# Freedom_E310.net
KiCad netlist of a schematic drawn in Altium Designer
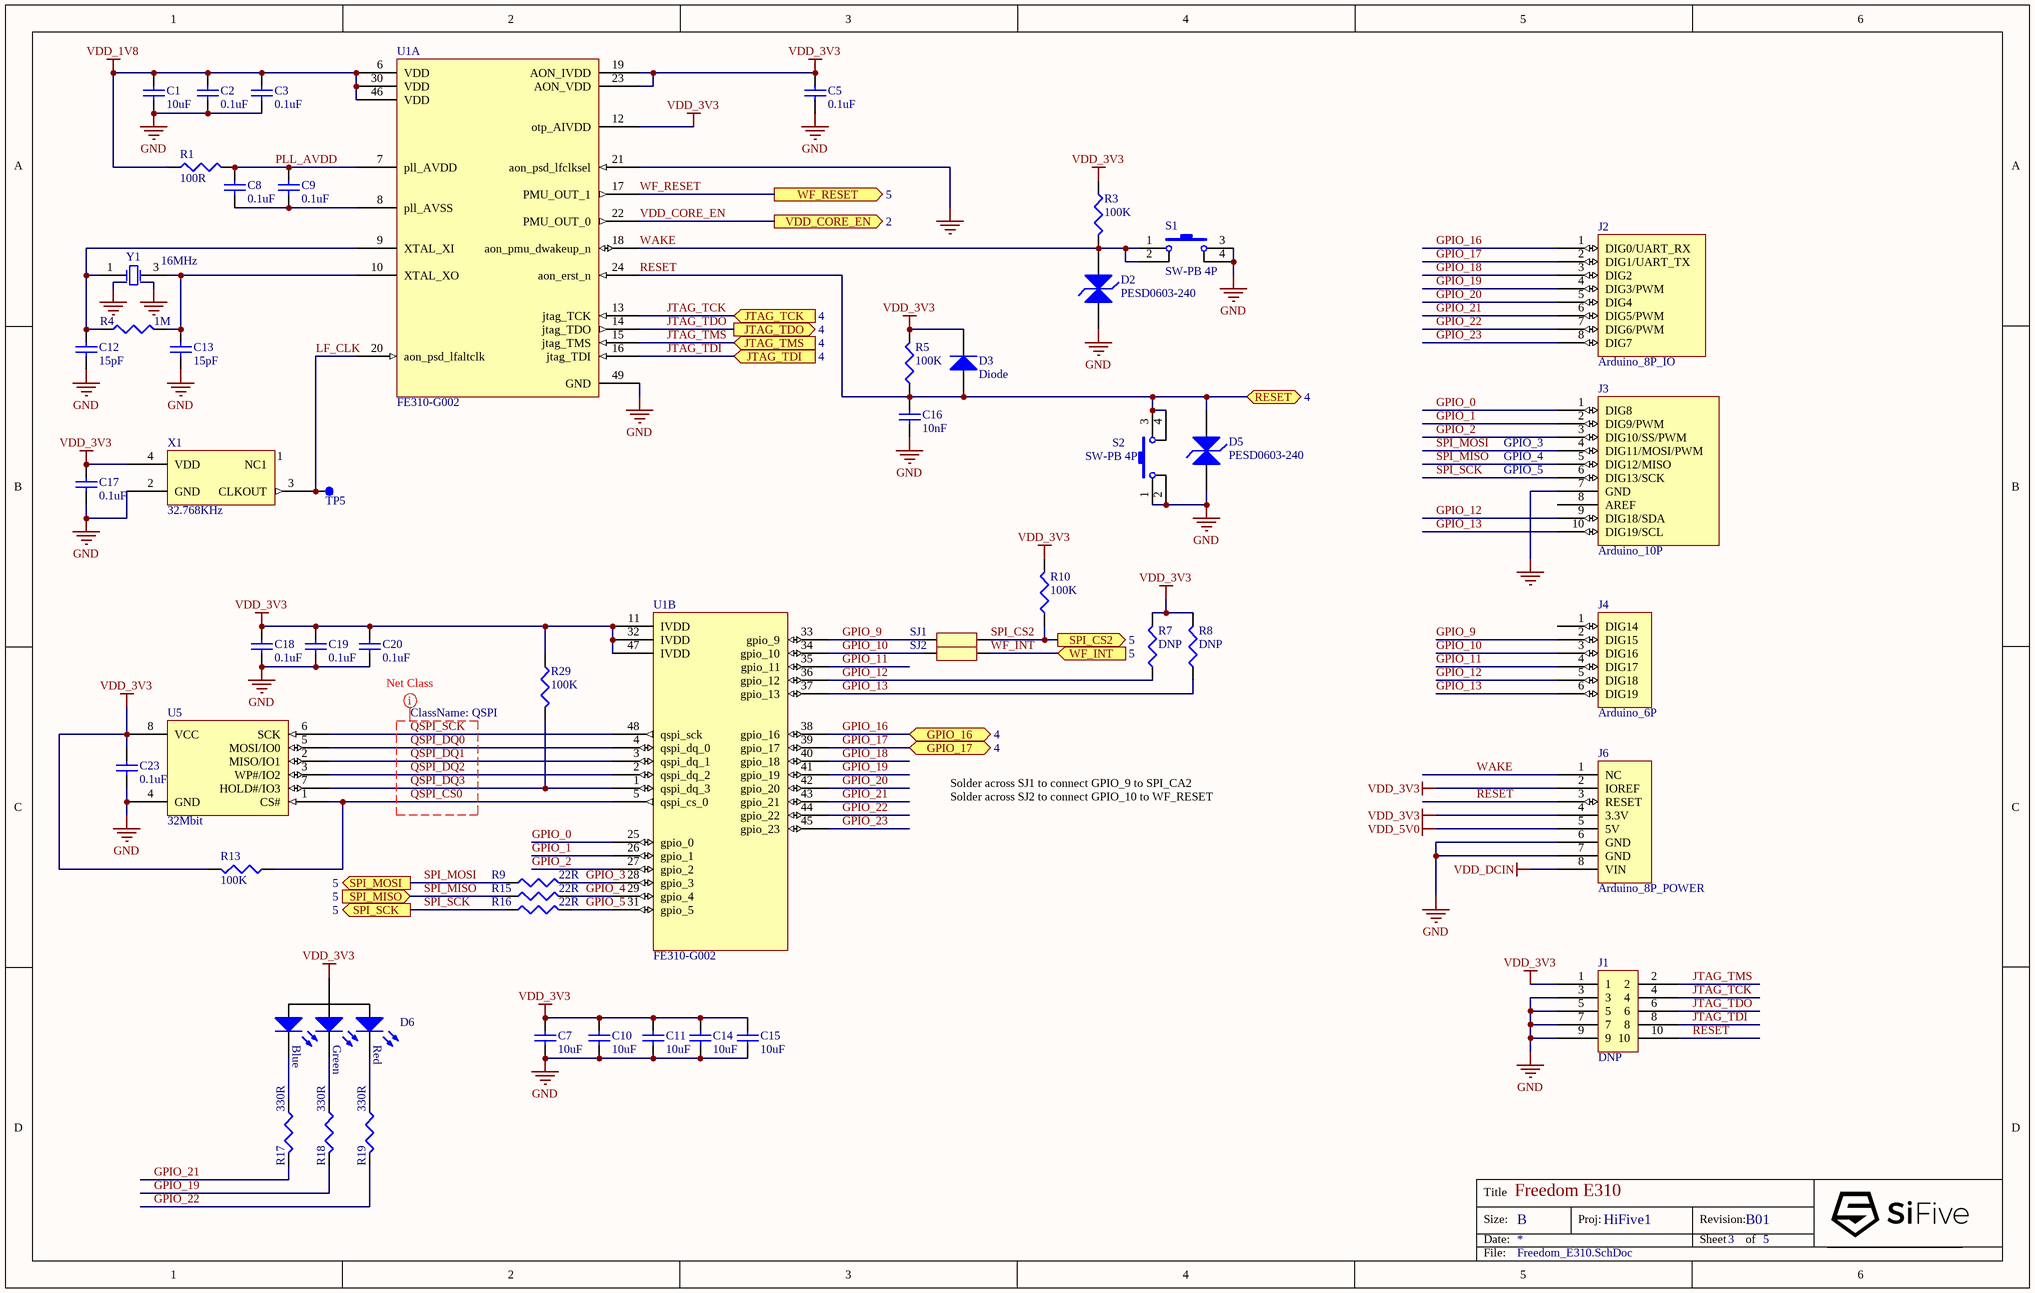
[diagram p0: Freedom_E310.SchDoc]

(export (version "E")
  (design (tool "Eeschema 10.0.6"))
  (components
    (comp (ref "C1")
      (value "10uF")
      (footprint "C0603")
      (description "CAP CER 10UF 10V X5R 0603")
      (fields (field (name "PART NUMBER") "C0100033") (field (name "MANUFACTURER") "Murata Electronics"))
      (libsource (lib "PartLibrary") (part "Capacitor - non polarized"))
    )
    (comp (ref "C2")
      (value "0.1uF")
      (footprint "C0402")
      (description "0.10µF 16V Ceramic Capacitor X7R 0402")
      (fields
        (field (name "PART NUMBER") "C0100004")
        (field (name "MANUFACTURER") "Samsung Electro-Mechanics")
      )
      (libsource (lib "PartLibrary") (part "Capacitor - non polarized"))
    )
    (comp (ref "C3")
      (value "0.1uF")
      (footprint "C0402")
      (description "0.10µF 16V Ceramic Capacitor X7R 0402")
      (fields
        (field (name "PART NUMBER") "C0100004")
        (field (name "MANUFACTURER") "Samsung Electro-Mechanics")
      )
      (libsource (lib "PartLibrary") (part "Capacitor - non polarized"))
    )
    (comp (ref "C5")
      (value "0.1uF")
      (footprint "C0402")
      (description "0.10µF 16V Ceramic Capacitor X7R 0402")
      (fields
        (field (name "PART NUMBER") "C0100004")
        (field (name "MANUFACTURER") "Samsung Electro-Mechanics")
      )
      (libsource (lib "PartLibrary") (part "Capacitor - non polarized"))
    )
    (comp (ref "C7")
      (value "10uF")
      (footprint "C0603")
      (description "CAP CER 10UF 10V X5R 0603")
      (fields (field (name "PART NUMBER") "C0100033") (field (name "MANUFACTURER") "Murata Electronics"))
      (libsource (lib "PartLibrary") (part "Capacitor - non polarized"))
    )
    (comp (ref "C8")
      (value "0.1uF")
      (footprint "C0402")
      (description "0.10µF 16V Ceramic Capacitor X7R 0402")
      (fields
        (field (name "PART NUMBER") "C0100004")
        (field (name "MANUFACTURER") "Samsung Electro-Mechanics")
      )
      (libsource (lib "PartLibrary") (part "Capacitor - non polarized"))
    )
    (comp (ref "C9")
      (value "0.1uF")
      (footprint "C0402")
      (description "0.10µF 16V Ceramic Capacitor X7R 0402")
      (fields
        (field (name "PART NUMBER") "C0100004")
        (field (name "MANUFACTURER") "Samsung Electro-Mechanics")
      )
      (libsource (lib "PartLibrary") (part "Capacitor - non polarized"))
    )
    (comp (ref "C10")
      (value "10uF")
      (footprint "C0603")
      (description "CAP CER 10UF 10V X5R 0603")
      (fields (field (name "PART NUMBER") "C0100033") (field (name "MANUFACTURER") "Murata Electronics"))
      (libsource (lib "PartLibrary") (part "Capacitor - non polarized"))
    )
    (comp (ref "C11")
      (value "10uF")
      (footprint "C0603")
      (description "CAP CER 10UF 10V X5R 0603")
      (fields (field (name "PART NUMBER") "C0100033") (field (name "MANUFACTURER") "Murata Electronics"))
      (libsource (lib "PartLibrary") (part "Capacitor - non polarized"))
    )
    (comp (ref "C12")
      (value "15pF")
      (footprint "C0402")
      (description "CAP CER 15PF 50V C0G/NPO 0402")
      (fields (field (name "PART NUMBER") "C0100038") (field (name "MANUFACTURER") "Yageo"))
      (libsource (lib "PartLibrary") (part "Capacitor - non polarized"))
    )
    (comp (ref "C13")
      (value "15pF")
      (footprint "C0402")
      (description "CAP CER 15PF 50V C0G/NPO 0402")
      (fields (field (name "PART NUMBER") "C0100038") (field (name "MANUFACTURER") "Yageo"))
      (libsource (lib "PartLibrary") (part "Capacitor - non polarized"))
    )
    (comp (ref "C14")
      (value "10uF")
      (footprint "C0603")
      (description "CAP CER 10UF 10V X5R 0603")
      (fields (field (name "PART NUMBER") "C0100033") (field (name "MANUFACTURER") "Murata Electronics"))
      (libsource (lib "PartLibrary") (part "Capacitor - non polarized"))
    )
    (comp (ref "C15")
      (value "10uF")
      (footprint "C0603")
      (description "CAP CER 10UF 10V X5R 0603")
      (fields (field (name "PART NUMBER") "C0100033") (field (name "MANUFACTURER") "Murata Electronics"))
      (libsource (lib "PartLibrary") (part "Capacitor - non polarized"))
    )
    (comp (ref "C16")
      (value "10nF")
      (footprint "C0402")
      (description "CAP CER 10000PF 50V X7R 0402")
      (fields
        (field (name "PART NUMBER") "C0100037")
        (field (name "MANUFACTURER") "Samsung Electro-Mechanics")
      )
      (libsource (lib "PartLibrary") (part "Capacitor - non polarized"))
    )
    (comp (ref "C17")
      (value "0.1uF")
      (footprint "C0402")
      (description "0.10µF 16V Ceramic Capacitor X7R 0402")
      (fields
        (field (name "PART NUMBER") "C0100004")
        (field (name "MANUFACTURER") "Samsung Electro-Mechanics")
      )
      (libsource (lib "PartLibrary") (part "Capacitor - non polarized"))
    )
    (comp (ref "C18")
      (value "0.1uF")
      (footprint "C0402")
      (description "0.10µF 16V Ceramic Capacitor X7R 0402")
      (fields
        (field (name "PART NUMBER") "C0100004")
        (field (name "MANUFACTURER") "Samsung Electro-Mechanics")
      )
      (libsource (lib "PartLibrary") (part "Capacitor - non polarized"))
    )
    (comp (ref "C19")
      (value "0.1uF")
      (footprint "C0402")
      (description "0.10µF 16V Ceramic Capacitor X7R 0402")
      (fields
        (field (name "PART NUMBER") "C0100004")
        (field (name "MANUFACTURER") "Samsung Electro-Mechanics")
      )
      (libsource (lib "PartLibrary") (part "Capacitor - non polarized"))
    )
    (comp (ref "C20")
      (value "0.1uF")
      (footprint "C0402")
      (description "0.10µF 16V Ceramic Capacitor X7R 0402")
      (fields
        (field (name "PART NUMBER") "C0100004")
        (field (name "MANUFACTURER") "Samsung Electro-Mechanics")
      )
      (libsource (lib "PartLibrary") (part "Capacitor - non polarized"))
    )
    (comp (ref "C23")
      (value "0.1uF")
      (footprint "C0402")
      (description "0.10µF 16V Ceramic Capacitor X7R 0402")
      (fields
        (field (name "PART NUMBER") "C0100004")
        (field (name "MANUFACTURER") "Samsung Electro-Mechanics")
      )
      (libsource (lib "PartLibrary") (part "Capacitor - non polarized"))
    )
    (comp (ref "D2")
      (value "PESD0603-240")
      (footprint "R0603")
      (description "TVS Diode 24VWM  45VClamp")
      (fields (field (name "PART NUMBER") "D0000013") (field (name "MANUFACTURER") "Littlefuse"))
      (libsource (lib "PartLibrary") (part "ESD Diode Bidirectional"))
    )
    (comp (ref "D3")
      (value "Diode")
      (footprint "SOD523")
      (description "Diode Standard 80V 125mA Surface Mount SOD-523")
      (fields (field (name "PART NUMBER") "D0000001") (field (name "MANUFACTURER") "Diodes Incorporated"))
      (libsource (lib "PartLibrary") (part "Diode"))
    )
    (comp (ref "D5")
      (value "PESD0603-240")
      (footprint "R0603")
      (description "TVS Diode 24VWM  45VClamp")
      (fields (field (name "PART NUMBER") "D0000013") (field (name "MANUFACTURER") "Littlefuse"))
      (libsource (lib "PartLibrary") (part "ESD Diode Bidirectional"))
    )
    (comp (ref "D6")
      (value "LED_RGB_LTST-C19HE1WT")
      (footprint "LED0606")
      (fields (field (name "PART NUMBER") "E0000005") (field (name "MANUFACTURER") "Lite-on Inc."))
      (libsource (lib "PartLibrary") (part "LED_RGB_LTST-C19HE1WT"))
    )
    (comp (ref "J1")
      (value "DNP")
      (footprint "CNC_3221-10-0300-00")
      (description "Connector Header Surface Mount 10 position 0.050\" (1.27mm)")
      (fields (field (name "PART NUMBER") "J0000049") (field (name "MANUFACTURER") "CNC Tech"))
      (libsource (lib "PartLibrary") (part "Header 2x5"))
    )
    (comp (ref "J2")
      (value "Arduino_8P_IO")
      (footprint "Arduino_8P_IO")
      (description "Arduino 8 Pin I/O Connector")
      (fields
        (field (name "PART NUMBER") "J0000005")
        (field (name "MANUFACTURER") "Sullins Connector Solutions")
      )
      (libsource (lib "PartLibrary") (part "Arduino_8P_IO"))
    )
    (comp (ref "J3")
      (value "Arduino_10P")
      (footprint "Arduino_10P")
      (description "Arduino 10 Pin Connector")
      (fields
        (field (name "PART NUMBER") "J0000007")
        (field (name "MANUFACTURER") "Sullins Connector Solutions")
      )
      (libsource (lib "PartLibrary") (part "Arduino_10P"))
    )
    (comp (ref "J4")
      (value "Arduino_6P")
      (footprint "Arduino_6P")
      (description "Arduino 6 Pin Connector")
      (fields
        (field (name "PART NUMBER") "J0000004")
        (field (name "MANUFACTURER") "Sullins Connector Solutions")
      )
      (libsource (lib "PartLibrary") (part "Arduino_6P"))
    )
    (comp (ref "J6")
      (value "Arduino_8P_POWER")
      (footprint "Arduino_8P_POWER")
      (description "Arduino 8 Pin Power Connector")
      (fields
        (field (name "PART NUMBER") "J0000006")
        (field (name "MANUFACTURER") "Sullins Connector Solutions")
      )
      (libsource (lib "PartLibrary") (part "Arduino_8P_POWER"))
    )
    (comp (ref "R1")
      (value "100R")
      (footprint "R0402")
      (description "RES SMD 100 OHM 1% 1/16W 0402")
      (fields (field (name "PART NUMBER") "R0000020") (field (name "MANUFACTURER") "Yageo"))
      (libsource (lib "PartLibrary") (part "Resistor"))
    )
    (comp (ref "R3")
      (value "100K")
      (footprint "R0402")
      (description "RES SMD 100K OHM 1% 1/16W 0402")
      (fields (field (name "PART NUMBER") "R0000012") (field (name "MANUFACTURER") "Yageo"))
      (libsource (lib "PartLibrary") (part "Resistor"))
    )
    (comp (ref "R4")
      (value "1M")
      (footprint "R0402")
      (description "RES SMD 1M OHM 1% 1/16W 0402")
      (fields (field (name "PART NUMBER") "R0000021") (field (name "MANUFACTURER") "Yageo"))
      (libsource (lib "PartLibrary") (part "Resistor"))
    )
    (comp (ref "R5")
      (value "100K")
      (footprint "R0402")
      (description "RES SMD 100K OHM 1% 1/16W 0402")
      (fields (field (name "PART NUMBER") "R0000012") (field (name "MANUFACTURER") "Yageo"))
      (libsource (lib "PartLibrary") (part "Resistor"))
    )
    (comp (ref "R7")
      (value "DNP")
      (footprint "R0402")
      (description "RES SMD 2K OHM 1% 1/16W 0402")
      (fields (field (name "PART NUMBER") "R0000025") (field (name "MANUFACTURER") "Yageo"))
      (libsource (lib "PartLibrary") (part "Resistor"))
    )
    (comp (ref "R8")
      (value "DNP")
      (footprint "R0402")
      (description "RES SMD 2K OHM 1% 1/16W 0402")
      (fields (field (name "PART NUMBER") "R0000025") (field (name "MANUFACTURER") "Yageo"))
      (libsource (lib "PartLibrary") (part "Resistor"))
    )
    (comp (ref "R9")
      (value "22R")
      (footprint "R0402")
      (description "RES SMD 22 OHM 1% 1/16W 0402")
      (fields (field (name "PART NUMBER") "R0000022") (field (name "MANUFACTURER") "Yageo"))
      (libsource (lib "PartLibrary") (part "Resistor"))
    )
    (comp (ref "R10")
      (value "100K")
      (footprint "R0402")
      (description "RES SMD 100K OHM 1% 1/16W 0402")
      (fields (field (name "PART NUMBER") "R0000012") (field (name "MANUFACTURER") "Yageo"))
      (libsource (lib "PartLibrary") (part "Resistor"))
    )
    (comp (ref "R13")
      (value "100K")
      (footprint "R0402")
      (description "RES SMD 100K OHM 1% 1/16W 0402")
      (fields (field (name "PART NUMBER") "R0000012") (field (name "MANUFACTURER") "Yageo"))
      (libsource (lib "PartLibrary") (part "Resistor"))
    )
    (comp (ref "R15")
      (value "22R")
      (footprint "R0402")
      (description "RES SMD 22 OHM 1% 1/16W 0402")
      (fields (field (name "PART NUMBER") "R0000022") (field (name "MANUFACTURER") "Yageo"))
      (libsource (lib "PartLibrary") (part "Resistor"))
    )
    (comp (ref "R16")
      (value "22R")
      (footprint "R0402")
      (description "RES SMD 22 OHM 1% 1/16W 0402")
      (fields (field (name "PART NUMBER") "R0000022") (field (name "MANUFACTURER") "Yageo"))
      (libsource (lib "PartLibrary") (part "Resistor"))
    )
    (comp (ref "R17")
      (value "330R")
      (footprint "R0402")
      (description "RES SMD 330 OHM 1% 1/16W 0402")
      (fields (field (name "PART NUMBER") "R0000026") (field (name "MANUFACTURER") "Yageo"))
      (libsource (lib "PartLibrary") (part "Resistor"))
    )
    (comp (ref "R18")
      (value "330R")
      (footprint "R0402")
      (description "RES SMD 330 OHM 1% 1/16W 0402")
      (fields (field (name "PART NUMBER") "R0000026") (field (name "MANUFACTURER") "Yageo"))
      (libsource (lib "PartLibrary") (part "Resistor"))
    )
    (comp (ref "R19")
      (value "330R")
      (footprint "R0402")
      (description "RES SMD 330 OHM 1% 1/16W 0402")
      (fields (field (name "PART NUMBER") "R0000026") (field (name "MANUFACTURER") "Yageo"))
      (libsource (lib "PartLibrary") (part "Resistor"))
    )
    (comp (ref "R29")
      (value "100K")
      (footprint "R0402")
      (description "RES SMD 100K OHM 1% 1/16W 0402")
      (fields (field (name "PART NUMBER") "R0000012") (field (name "MANUFACTURER") "Yageo"))
      (libsource (lib "PartLibrary") (part "Resistor"))
    )
    (comp (ref "S1")
      (value "SW-PB 4P")
      (footprint "PTS645_SMT")
      (description "Blue Tactile Switch SPST-NO Top Actuated Surface Mount")
      (fields (field (name "PART NUMBER") "M0000004") (field (name "MANUFACTURER") "C & K Components"))
      (libsource (lib "PartLibrary") (part "SW-PB 4P"))
    )
    (comp (ref "S2")
      (value "SW-PB 4P")
      (footprint "PTS645_SMT")
      (description "Red Tactile Switch SPST-NO Top Actuated Surface Mount")
      (fields (field (name "PART NUMBER") "M0000003") (field (name "MANUFACTURER") "C & K Components"))
      (libsource (lib "PartLibrary") (part "SW-PB 4P"))
    )
    (comp (ref "SJ1")
      (value "Solder Jumper")
      (footprint "SJ0805")
      (description "Solder Bridge 0805")
      (fields (field (name "PART NUMBER") "M0000009") (field (name "MANUFACTURER") "None"))
      (libsource (lib "PartLibrary") (part "Solder Jumper"))
    )
    (comp (ref "SJ2")
      (value "Solder Jumper")
      (footprint "SJ0805")
      (description "Solder Bridge 0805")
      (fields (field (name "PART NUMBER") "M0000009") (field (name "MANUFACTURER") "None"))
      (libsource (lib "PartLibrary") (part "Solder Jumper"))
    )
    (comp (ref "TP5")
      (value "Testpoint")
      (footprint "Testpoint_SMT")
      (description "Test Point SMT")
      (fields (field (name "PART NUMBER") "M0000002"))
      (libsource (lib "PartLibrary") (part "Testpoint"))
    )
    (comp (ref "U1")
      (value "FE310-G002")
      (footprint "QFN48_40P600X600X90_HS-49")
      (description "SiFive Freedom E310 Microcontroller")
      (fields (field (name "PART NUMBER") "U0000050") (field (name "MANUFACTURER") "SiFive"))
      (libsource (lib "PartLibrary") (part "Freedom-E300 48Pin"))
    )
    (comp (ref "U5")
      (value "32Mbit")
      (footprint "SOIC127P790X216-8N")
      (description "IC FLASH 32MBIT 133MHZ 8SOIC 2.3 V ~ 3.6 V")
      (fields (field (name "PART NUMBER") "U0000019") (field (name "MANUFACTURER") "ISSI"))
      (libsource (lib "PartLibrary") (part "QuadSPI_8Pin"))
    )
    (comp (ref "X1")
      (value "32.768KHz")
      (footprint "SiTime2012")
      (description "32.768kHz LVCMOS MEMS (Silicon) Oscillator Surface Mount 1.2 V ~ 3.63 V 1.3µA")
      (fields (field (name "PART NUMBER") "X0000014") (field (name "MANUFACTURER") "SiTime"))
      (libsource (lib "PartLibrary") (part "OSC_SiTime_2012"))
    )
    (comp (ref "Y1")
      (value "16MHz")
      (footprint "X3225")
      (description "16MHz ±10ppm Crystal 9pF 60 Ohm")
      (fields (field (name "PART NUMBER") "X0000015") (field (name "MANUFACTURER") "Epson"))
      (libsource (lib "PartLibrary") (part "XTAL 4p"))
    )
  )
  (nets
    (net (code "1") (name "/GPIO_0") (class "Default")
      (node (ref "J3") (pin "1") (pinfunction "DIG8_1") (pintype "bidirectional"))
      (node (ref "U1") (pin "25") (pinfunction "gpio_0_25") (pintype "bidirectional"))
    )
    (net (code "2") (name "/GPIO_1") (class "Default")
      (node (ref "J3") (pin "2") (pinfunction "DIG9/PWM_2") (pintype "bidirectional"))
      (node (ref "U1") (pin "26") (pinfunction "gpio_1_26") (pintype "bidirectional"))
    )
    (net (code "3") (name "/GPIO_2") (class "Default")
      (node (ref "J3") (pin "3") (pinfunction "DIG10/SS/PWM_3") (pintype "bidirectional"))
      (node (ref "U1") (pin "27") (pinfunction "gpio_2_27") (pintype "bidirectional"))
    )
    (net (code "4") (name "/GPIO_3") (class "Default")
      (node (ref "R9") (pin "2") (pinfunction "2_2") (pintype "passive"))
      (node (ref "U1") (pin "28") (pinfunction "gpio_3_28") (pintype "bidirectional"))
    )
    (net (code "5") (name "/GPIO_4") (class "Default")
      (node (ref "R15") (pin "2") (pinfunction "2_2") (pintype "passive"))
      (node (ref "U1") (pin "29") (pinfunction "gpio_4_29") (pintype "bidirectional"))
    )
    (net (code "6") (name "/GPIO_5") (class "Default")
      (node (ref "R16") (pin "2") (pinfunction "2_2") (pintype "passive"))
      (node (ref "U1") (pin "31") (pinfunction "gpio_5_31") (pintype "bidirectional"))
    )
    (net (code "7") (name "/GPIO_9") (class "Default")
      (node (ref "J4") (pin "2") (pinfunction "DIG15_2") (pintype "bidirectional"))
      (node (ref "SJ1") (pin "1") (pinfunction "1_1") (pintype "passive"))
      (node (ref "U1") (pin "33") (pinfunction "gpio_9_33") (pintype "bidirectional"))
    )
    (net (code "8") (name "/GPIO_10") (class "Default")
      (node (ref "J4") (pin "3") (pinfunction "DIG16_3") (pintype "bidirectional"))
      (node (ref "SJ2") (pin "1") (pinfunction "1_1") (pintype "passive"))
      (node (ref "U1") (pin "34") (pinfunction "gpio_10_34") (pintype "bidirectional"))
    )
    (net (code "9") (name "/GPIO_11") (class "Default")
      (node (ref "J4") (pin "4") (pinfunction "DIG17_4") (pintype "bidirectional"))
      (node (ref "U1") (pin "35") (pinfunction "gpio_11_35") (pintype "bidirectional"))
    )
    (net (code "10") (name "/GPIO_12") (class "Default")
      (node (ref "J3") (pin "9") (pinfunction "DIG18/SDA_9") (pintype "bidirectional"))
      (node (ref "J4") (pin "5") (pinfunction "DIG18_5") (pintype "bidirectional"))
      (node (ref "R7") (pin "1") (pinfunction "1_1") (pintype "passive"))
      (node (ref "U1") (pin "36") (pinfunction "gpio_12_36") (pintype "bidirectional"))
    )
    (net (code "11") (name "/GPIO_13") (class "Default")
      (node (ref "J3") (pin "10") (pinfunction "DIG19/SCL_10") (pintype "bidirectional"))
      (node (ref "J4") (pin "6") (pinfunction "DIG19_6") (pintype "bidirectional"))
      (node (ref "R8") (pin "1") (pinfunction "1_1") (pintype "passive"))
      (node (ref "U1") (pin "37") (pinfunction "gpio_13_37") (pintype "bidirectional"))
    )
    (net (code "12") (name "/GPIO_16") (class "Default")
      (node (ref "J2") (pin "1") (pinfunction "DIG0/UART_RX_1") (pintype "bidirectional"))
      (node (ref "U1") (pin "38") (pinfunction "gpio_16_38") (pintype "bidirectional"))
    )
    (net (code "13") (name "/GPIO_17") (class "Default")
      (node (ref "J2") (pin "2") (pinfunction "DIG1/UART_TX_2") (pintype "bidirectional"))
      (node (ref "U1") (pin "39") (pinfunction "gpio_17_39") (pintype "bidirectional"))
    )
    (net (code "14") (name "/GPIO_18") (class "Default")
      (node (ref "J2") (pin "3") (pinfunction "DIG2_3") (pintype "bidirectional"))
      (node (ref "U1") (pin "40") (pinfunction "gpio_18_40") (pintype "bidirectional"))
    )
    (net (code "15") (name "/GPIO_19") (class "Default")
      (node (ref "J2") (pin "4") (pinfunction "DIG3/PWM_4") (pintype "bidirectional"))
      (node (ref "R18") (pin "2") (pinfunction "2_2") (pintype "passive"))
      (node (ref "U1") (pin "41") (pinfunction "gpio_19_41") (pintype "bidirectional"))
    )
    (net (code "16") (name "/GPIO_20") (class "Default")
      (node (ref "J2") (pin "5") (pinfunction "DIG4_5") (pintype "bidirectional"))
      (node (ref "U1") (pin "42") (pinfunction "gpio_20_42") (pintype "bidirectional"))
    )
    (net (code "17") (name "/GPIO_21") (class "Default")
      (node (ref "J2") (pin "6") (pinfunction "DIG5/PWM_6") (pintype "bidirectional"))
      (node (ref "R17") (pin "2") (pinfunction "2_2") (pintype "passive"))
      (node (ref "U1") (pin "43") (pinfunction "gpio_21_43") (pintype "bidirectional"))
    )
    (net (code "18") (name "/GPIO_22") (class "Default")
      (node (ref "J2") (pin "7") (pinfunction "DIG6/PWM_7") (pintype "bidirectional"))
      (node (ref "R19") (pin "2") (pinfunction "2_2") (pintype "passive"))
      (node (ref "U1") (pin "44") (pinfunction "gpio_22_44") (pintype "bidirectional"))
    )
    (net (code "19") (name "/GPIO_23") (class "Default")
      (node (ref "J2") (pin "8") (pinfunction "DIG7_8") (pintype "bidirectional"))
      (node (ref "U1") (pin "45") (pinfunction "gpio_23_45") (pintype "bidirectional"))
    )
    (net (code "20") (name "/JTAG_TCK") (class "Default")
      (node (ref "J1") (pin "4") (pinfunction "4_4") (pintype "passive"))
      (node (ref "U1") (pin "13") (pinfunction "jtag_TCK_13") (pintype "input"))
    )
    (net (code "21") (name "/JTAG_TDI") (class "Default")
      (node (ref "J1") (pin "8") (pinfunction "8_8") (pintype "passive"))
      (node (ref "U1") (pin "16") (pinfunction "jtag_TDI_16") (pintype "input"))
    )
    (net (code "22") (name "/JTAG_TDO") (class "Default")
      (node (ref "J1") (pin "6") (pinfunction "6_6") (pintype "passive"))
      (node (ref "U1") (pin "14") (pinfunction "jtag_TDO_14") (pintype "output"))
    )
    (net (code "23") (name "/JTAG_TMS") (class "Default")
      (node (ref "J1") (pin "2") (pinfunction "2_2") (pintype "passive"))
      (node (ref "U1") (pin "15") (pinfunction "jtag_TMS_15") (pintype "input"))
    )
    (net (code "24") (name "/LF_CLK") (class "Default")
      (node (ref "TP5") (pin "1") (pinfunction "1_1") (pintype "passive"))
      (node (ref "U1") (pin "20") (pinfunction "aon_psd_lfaltclk_20") (pintype "input"))
      (node (ref "X1") (pin "3") (pinfunction "CLKOUT_3") (pintype "output"))
    )
    (net (code "25") (name "/PLL_AVDD") (class "Default")
      (node (ref "C8") (pin "2") (pinfunction "2_2") (pintype "passive"))
      (node (ref "C9") (pin "2") (pinfunction "2_2") (pintype "passive"))
      (node (ref "R1") (pin "2") (pinfunction "2_2") (pintype "passive"))
      (node (ref "U1") (pin "7") (pinfunction "pll_AVDD_7") (pintype "power_in"))
    )
    (net (code "26") (name "/QSPI_CS0") (class "Default")
      (node (ref "R13") (pin "1") (pinfunction "1_1") (pintype "passive"))
      (node (ref "U1") (pin "5") (pinfunction "qspi_cs_0_5") (pintype "output"))
      (node (ref "U5") (pin "1") (pinfunction "CS#_1") (pintype "input"))
    )
    (net (code "27") (name "/QSPI_DQ0") (class "Default")
      (node (ref "U1") (pin "4") (pinfunction "qspi_dq_0_4") (pintype "bidirectional"))
      (node (ref "U5") (pin "5") (pinfunction "MOSI/IO0_5") (pintype "bidirectional"))
    )
    (net (code "28") (name "/QSPI_DQ1") (class "Default")
      (node (ref "U1") (pin "3") (pinfunction "qspi_dq_1_3") (pintype "bidirectional"))
      (node (ref "U5") (pin "2") (pinfunction "MISO/IO1_2") (pintype "bidirectional"))
    )
    (net (code "29") (name "/QSPI_DQ2") (class "Default")
      (node (ref "U1") (pin "2") (pinfunction "qspi_dq_2_2") (pintype "bidirectional"))
      (node (ref "U5") (pin "3") (pinfunction "WP#/IO2_3") (pintype "bidirectional"))
    )
    (net (code "30") (name "/QSPI_DQ3") (class "Default")
      (node (ref "R29") (pin "2") (pinfunction "2_2") (pintype "passive"))
      (node (ref "U1") (pin "1") (pinfunction "qspi_dq_3_1") (pintype "bidirectional"))
      (node (ref "U5") (pin "7") (pinfunction "HOLD#/IO3_7") (pintype "bidirectional"))
    )
    (net (code "31") (name "/QSPI_SCK") (class "Default")
      (node (ref "U1") (pin "48") (pinfunction "qspi_sck_48") (pintype "output"))
      (node (ref "U5") (pin "6") (pinfunction "SCK_6") (pintype "input"))
    )
    (net (code "32") (name "/RESET") (class "Default")
      (node (ref "C16") (pin "1") (pinfunction "1_1") (pintype "passive"))
      (node (ref "D3") (pin "2") (pinfunction "A_2") (pintype "passive"))
      (node (ref "D5") (pin "1") (pinfunction "1_1") (pintype "passive"))
      (node (ref "J1") (pin "10") (pinfunction "10_10") (pintype "passive"))
      (node (ref "J6") (pin "3") (pinfunction "RESET_3") (pintype "bidirectional"))
      (node (ref "R5") (pin "1") (pinfunction "1_1") (pintype "passive"))
      (node (ref "S2") (pin "3") (pinfunction "3_3") (pintype "passive"))
      (node (ref "S2") (pin "4") (pinfunction "4_4") (pintype "passive"))
      (node (ref "U1") (pin "24") (pinfunction "aon_erst_n_24") (pintype "input"))
    )
    (net (code "33") (name "/SPI_CS2") (class "Default")
      (node (ref "R10") (pin "1") (pinfunction "1_1") (pintype "passive"))
      (node (ref "SJ1") (pin "2") (pinfunction "2_2") (pintype "passive"))
    )
    (net (code "34") (name "/SPI_MISO") (class "Default")
      (node (ref "J3") (pin "5") (pinfunction "DIG12/MISO_5") (pintype "bidirectional"))
      (node (ref "R15") (pin "1") (pinfunction "1_1") (pintype "passive"))
    )
    (net (code "35") (name "/SPI_MOSI") (class "Default")
      (node (ref "J3") (pin "4") (pinfunction "DIG11/MOSI/PWM_4") (pintype "bidirectional"))
      (node (ref "R9") (pin "1") (pinfunction "1_1") (pintype "passive"))
    )
    (net (code "36") (name "/SPI_SCK") (class "Default")
      (node (ref "J3") (pin "6") (pinfunction "DIG13/SCK_6") (pintype "bidirectional"))
      (node (ref "R16") (pin "1") (pinfunction "1_1") (pintype "passive"))
    )
    (net (code "37") (name "/VDD_CORE_EN") (class "Default")
      (node (ref "U1") (pin "22") (pinfunction "PMU_OUT_0_22") (pintype "output"))
    )
    (net (code "38") (name "/WAKE") (class "Default")
      (node (ref "D2") (pin "1") (pinfunction "1_1") (pintype "passive"))
      (node (ref "J6") (pin "1") (pinfunction "NC_1") (pintype "passive"))
      (node (ref "R3") (pin "2") (pinfunction "2_2") (pintype "passive"))
      (node (ref "S1") (pin "1") (pinfunction "1_1") (pintype "passive"))
      (node (ref "S1") (pin "2") (pinfunction "2_2") (pintype "passive"))
      (node (ref "U1") (pin "18") (pinfunction "aon_pmu_dwakeup_n_18") (pintype "bidirectional"))
    )
    (net (code "39") (name "/WF_INT") (class "Default")
      (node (ref "SJ2") (pin "2") (pinfunction "2_2") (pintype "passive"))
    )
    (net (code "40") (name "/WF_RESET") (class "Default")
      (node (ref "U1") (pin "17") (pinfunction "PMU_OUT_1_17") (pintype "output"))
    )
    (net (code "41") (name "GND") (class "Default")
      (node (ref "C1") (pin "2") (pinfunction "2_2") (pintype "passive"))
      (node (ref "C10") (pin "2") (pinfunction "2_2") (pintype "passive"))
      (node (ref "C11") (pin "2") (pinfunction "2_2") (pintype "passive"))
      (node (ref "C12") (pin "2") (pinfunction "2_2") (pintype "passive"))
      (node (ref "C13") (pin "2") (pinfunction "2_2") (pintype "passive"))
      (node (ref "C14") (pin "2") (pinfunction "2_2") (pintype "passive"))
      (node (ref "C15") (pin "2") (pinfunction "2_2") (pintype "passive"))
      (node (ref "C16") (pin "2") (pinfunction "2_2") (pintype "passive"))
      (node (ref "C17") (pin "1") (pinfunction "1_1") (pintype "passive"))
      (node (ref "C18") (pin "1") (pinfunction "1_1") (pintype "passive"))
      (node (ref "C19") (pin "1") (pinfunction "1_1") (pintype "passive"))
      (node (ref "C2") (pin "1") (pinfunction "1_1") (pintype "passive"))
      (node (ref "C20") (pin "1") (pinfunction "1_1") (pintype "passive"))
      (node (ref "C23") (pin "1") (pinfunction "1_1") (pintype "passive"))
      (node (ref "C3") (pin "1") (pinfunction "1_1") (pintype "passive"))
      (node (ref "C5") (pin "1") (pinfunction "1_1") (pintype "passive"))
      (node (ref "C7") (pin "2") (pinfunction "2_2") (pintype "passive"))
      (node (ref "D2") (pin "2") (pinfunction "2_2") (pintype "passive"))
      (node (ref "D5") (pin "2") (pinfunction "2_2") (pintype "passive"))
      (node (ref "J1") (pin "3") (pinfunction "3_3") (pintype "passive"))
      (node (ref "J1") (pin "5") (pinfunction "5_5") (pintype "passive"))
      (node (ref "J1") (pin "7") (pinfunction "7_7") (pintype "passive"))
      (node (ref "J1") (pin "9") (pinfunction "9_9") (pintype "passive"))
      (node (ref "J3") (pin "7") (pinfunction "GND_7") (pintype "passive"))
      (node (ref "J6") (pin "6") (pinfunction "GND_6") (pintype "passive"))
      (node (ref "J6") (pin "7") (pinfunction "GND_7") (pintype "passive"))
      (node (ref "S1") (pin "3") (pinfunction "3_3") (pintype "passive"))
      (node (ref "S1") (pin "4") (pinfunction "4_4") (pintype "passive"))
      (node (ref "S2") (pin "1") (pinfunction "1_1") (pintype "passive"))
      (node (ref "S2") (pin "2") (pinfunction "2_2") (pintype "passive"))
      (node (ref "U1") (pin "21") (pinfunction "aon_psd_lfclksel_21") (pintype "input"))
      (node (ref "U1") (pin "49") (pinfunction "GND_49") (pintype "passive"))
      (node (ref "U5") (pin "4") (pinfunction "GND_4") (pintype "passive"))
      (node (ref "X1") (pin "2") (pinfunction "GND_2") (pintype "passive"))
      (node (ref "Y1") (pin "2") (pinfunction "NC1_2") (pintype "passive"))
      (node (ref "Y1") (pin "4") (pinfunction "NC2_4") (pintype "passive"))
    )
    (net (code "42") (name "Net-(D6-BlueK)") (class "Default")
      (node (ref "D6") (pin "3") (pinfunction "BlueK_3") (pintype "passive"))
      (node (ref "R17") (pin "1") (pinfunction "1_1") (pintype "passive"))
    )
    (net (code "43") (name "Net-(D6-GreenK)") (class "Default")
      (node (ref "D6") (pin "2") (pinfunction "GreenK_2") (pintype "passive"))
      (node (ref "R18") (pin "1") (pinfunction "1_1") (pintype "passive"))
    )
    (net (code "44") (name "Net-(D6-RedK)") (class "Default")
      (node (ref "D6") (pin "1") (pinfunction "RedK_1") (pintype "passive"))
      (node (ref "R19") (pin "1") (pinfunction "1_1") (pintype "passive"))
    )
    (net (code "45") (name "Net-(U1A-XTAL_XI)") (class "Default")
      (node (ref "C12") (pin "1") (pinfunction "1_1") (pintype "passive"))
      (node (ref "R4") (pin "1") (pinfunction "1_1") (pintype "passive"))
      (node (ref "U1") (pin "9") (pinfunction "XTAL_XI_9") (pintype "passive"))
      (node (ref "Y1") (pin "1") (pinfunction "OSC1_1") (pintype "passive"))
    )
    (net (code "46") (name "Net-(U1A-XTAL_XO)") (class "Default")
      (node (ref "C13") (pin "1") (pinfunction "1_1") (pintype "passive"))
      (node (ref "R4") (pin "2") (pinfunction "2_2") (pintype "passive"))
      (node (ref "U1") (pin "10") (pinfunction "XTAL_XO_10") (pintype "passive"))
      (node (ref "Y1") (pin "3") (pinfunction "OSC2_3") (pintype "passive"))
    )
    (net (code "47") (name "Net-(U1A-pll_AVSS)") (class "Default")
      (node (ref "C8") (pin "1") (pinfunction "1_1") (pintype "passive"))
      (node (ref "C9") (pin "1") (pinfunction "1_1") (pintype "passive"))
      (node (ref "U1") (pin "8") (pinfunction "pll_AVSS_8") (pintype "passive"))
    )
    (net (code "48") (name "VDD_1V8") (class "Default")
      (node (ref "C1") (pin "1") (pinfunction "1_1") (pintype "passive"))
      (node (ref "C2") (pin "2") (pinfunction "2_2") (pintype "passive"))
      (node (ref "C3") (pin "2") (pinfunction "2_2") (pintype "passive"))
      (node (ref "R1") (pin "1") (pinfunction "1_1") (pintype "passive"))
      (node (ref "U1") (pin "30") (pinfunction "VDD_30") (pintype "power_in"))
      (node (ref "U1") (pin "46") (pinfunction "VDD_46") (pintype "power_in"))
      (node (ref "U1") (pin "6") (pinfunction "VDD_6") (pintype "power_in"))
    )
    (net (code "49") (name "VDD_3V3") (class "Default")
      (node (ref "C10") (pin "1") (pinfunction "1_1") (pintype "passive"))
      (node (ref "C11") (pin "1") (pinfunction "1_1") (pintype "passive"))
      (node (ref "C14") (pin "1") (pinfunction "1_1") (pintype "passive"))
      (node (ref "C15") (pin "1") (pinfunction "1_1") (pintype "passive"))
      (node (ref "C17") (pin "2") (pinfunction "2_2") (pintype "passive"))
      (node (ref "C18") (pin "2") (pinfunction "2_2") (pintype "passive"))
      (node (ref "C19") (pin "2") (pinfunction "2_2") (pintype "passive"))
      (node (ref "C20") (pin "2") (pinfunction "2_2") (pintype "passive"))
      (node (ref "C23") (pin "2") (pinfunction "2_2") (pintype "passive"))
      (node (ref "C5") (pin "2") (pinfunction "2_2") (pintype "passive"))
      (node (ref "C7") (pin "1") (pinfunction "1_1") (pintype "passive"))
      (node (ref "D3") (pin "1") (pinfunction "K_1") (pintype "passive"))
      (node (ref "D6") (pin "4") (pinfunction "A_4") (pintype "passive"))
      (node (ref "J1") (pin "1") (pinfunction "1_1") (pintype "passive"))
      (node (ref "J6") (pin "2") (pinfunction "IOREF_2") (pintype "passive"))
      (node (ref "J6") (pin "4") (pinfunction "3.3V_4") (pintype "power_in"))
      (node (ref "R10") (pin "2") (pinfunction "2_2") (pintype "passive"))
      (node (ref "R13") (pin "2") (pinfunction "2_2") (pintype "passive"))
      (node (ref "R29") (pin "1") (pinfunction "1_1") (pintype "passive"))
      (node (ref "R3") (pin "1") (pinfunction "1_1") (pintype "passive"))
      (node (ref "R5") (pin "2") (pinfunction "2_2") (pintype "passive"))
      (node (ref "R7") (pin "2") (pinfunction "2_2") (pintype "passive"))
      (node (ref "R8") (pin "2") (pinfunction "2_2") (pintype "passive"))
      (node (ref "U1") (pin "11") (pinfunction "IVDD_11") (pintype "power_in"))
      (node (ref "U1") (pin "12") (pinfunction "otp_AIVDD_12") (pintype "power_in"))
      (node (ref "U1") (pin "19") (pinfunction "AON_IVDD_19") (pintype "power_in"))
      (node (ref "U1") (pin "23") (pinfunction "AON_VDD_23") (pintype "power_in"))
      (node (ref "U1") (pin "32") (pinfunction "IVDD_32") (pintype "power_in"))
      (node (ref "U1") (pin "47") (pinfunction "IVDD_47") (pintype "power_in"))
      (node (ref "U5") (pin "8") (pinfunction "VCC_8") (pintype "power_in"))
      (node (ref "X1") (pin "4") (pinfunction "VDD_4") (pintype "power_in"))
    )
    (net (code "50") (name "VDD_5V0") (class "Default")
      (node (ref "J6") (pin "5") (pinfunction "5V_5") (pintype "power_in"))
    )
    (net (code "51") (name "VDD_DCIN") (class "Default")
      (node (ref "J6") (pin "8") (pinfunction "VIN_8") (pintype "power_in"))
    )
    (net (code "52") (name "unconnected-(J3-AREF-Pad8)") (class "Default")
      (node (ref "J3") (pin "8") (pinfunction "AREF_8") (pintype "passive"))
    )
    (net (code "53") (name "unconnected-(J4-DIG14-Pad1)") (class "Default")
      (node (ref "J4") (pin "1") (pinfunction "DIG14_1") (pintype "bidirectional"))
    )
    (net (code "54") (name "unconnected-(X1-NC1-Pad1)") (class "Default")
      (node (ref "X1") (pin "1") (pinfunction "NC1_1") (pintype "passive"))
    )
  )
)
